# Diagrama-Eduproto.net
KiCad netlist of a schematic drawn in EAGLE
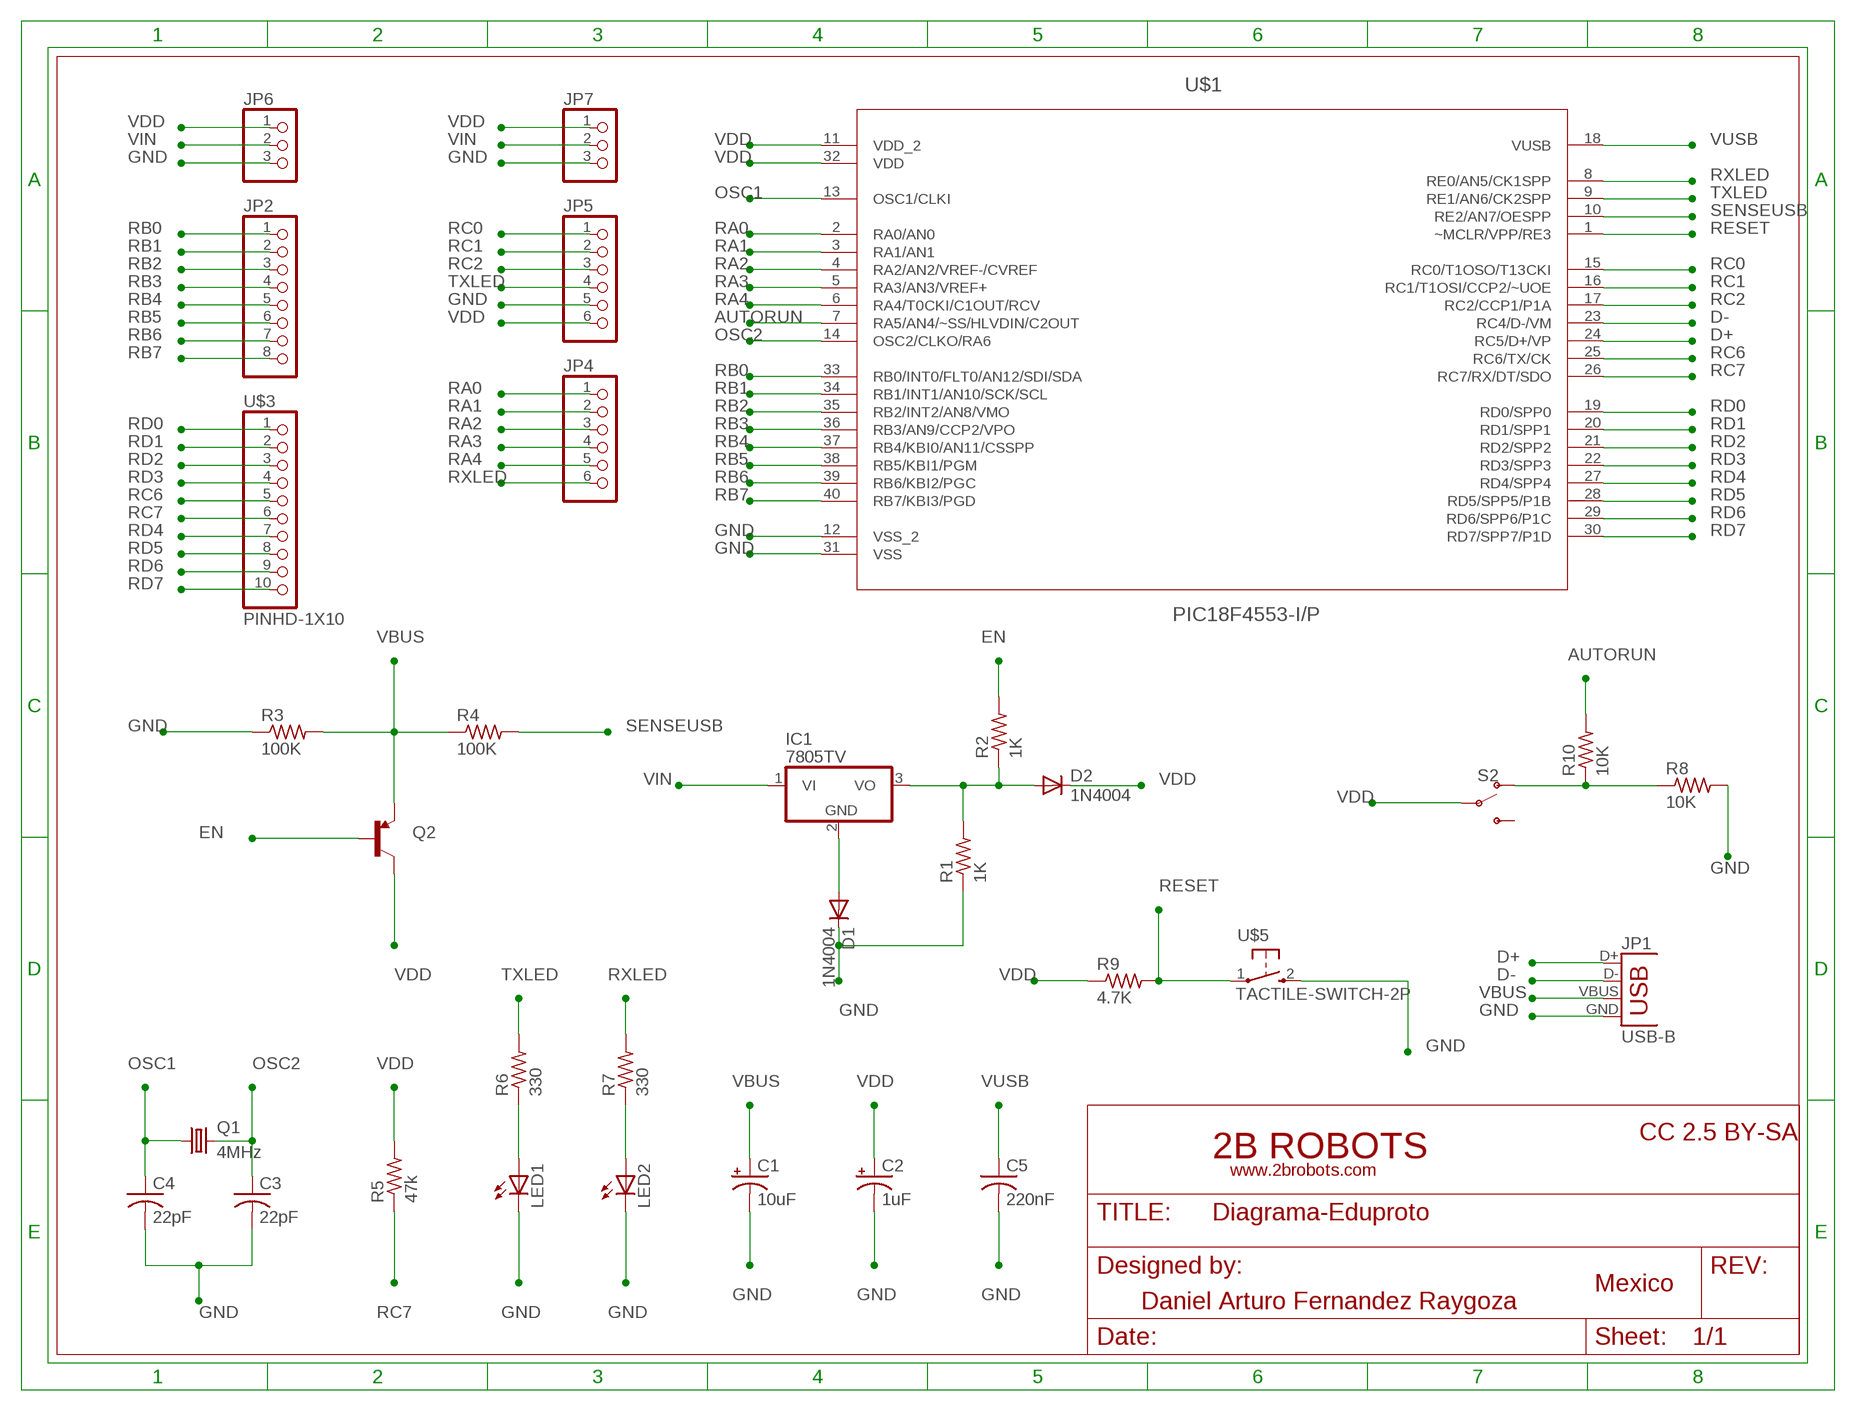
[diagram p0: schematic, sheet 1]

(export (version "E")
  (design (tool "Eeschema 10.0.6"))
  (components
    (comp (ref "C1")
      (value "10uF")
      (footprint "eagle-import:E1,8-4")
      (libsource (lib "eagle-import") (part "CPOL-USE1.8-4"))
    )
    (comp (ref "C2")
      (value "1uF")
      (footprint "eagle-import:E1,8-4")
      (libsource (lib "eagle-import") (part "CPOL-USE1.8-4"))
    )
    (comp (ref "C3")
      (value "22pF")
      (footprint "eagle-import:C050-024X044")
      (libsource (lib "eagle-import") (part "C-US050-024X044"))
    )
    (comp (ref "C4")
      (value "22pF")
      (footprint "eagle-import:C050-024X044")
      (libsource (lib "eagle-import") (part "C-US050-024X044"))
    )
    (comp (ref "C5")
      (value "220nF")
      (footprint "eagle-import:C050-025X075")
      (libsource (lib "eagle-import") (part "C-US050-025X075"))
    )
    (comp (ref "D1")
      (value "1N4004")
      (footprint "eagle-import:DO41-10")
      (libsource (lib "eagle-import") (part "1N4004"))
    )
    (comp (ref "D2")
      (value "1N4004")
      (footprint "eagle-import:DO41-10")
      (libsource (lib "eagle-import") (part "1N4004"))
    )
    (comp (ref "IC1")
      (value "7805TV")
      (footprint "eagle-import:TO220V")
      (libsource (lib "eagle-import") (part "78TV05"))
    )
    (comp (ref "JP1")
      (value "USB-B")
      (footprint "eagle-import:USB-B-PTH")
      (libsource (lib "eagle-import") (part "USBPTH"))
    )
    (comp (ref "JP2")
      (value "PINHD-1X8BIG")
      (footprint "eagle-import:1X08-BIG")
      (libsource (lib "eagle-import") (part "PINHD-1X8BIG"))
    )
    (comp (ref "JP4")
      (value "PINHD-1X6B")
      (footprint "eagle-import:1X06-BIG")
      (libsource (lib "eagle-import") (part "PINHD-1X6B"))
    )
    (comp (ref "JP5")
      (value "PINHD-1X6B")
      (footprint "eagle-import:1X06-BIG")
      (libsource (lib "eagle-import") (part "PINHD-1X6B"))
    )
    (comp (ref "JP6")
      (value "PINHD-1X3CB")
      (footprint "eagle-import:1X03-CLEANBIG")
      (libsource (lib "eagle-import") (part "PINHD-1X3CB"))
    )
    (comp (ref "JP7")
      (value "PINHD-1X3CB")
      (footprint "eagle-import:1X03-CLEANBIG")
      (libsource (lib "eagle-import") (part "PINHD-1X3CB"))
    )
    (comp (ref "LED1")
      (value "LED5MM")
      (footprint "eagle-import:LED5MM")
      (libsource (lib "eagle-import") (part "LED5MM"))
    )
    (comp (ref "LED2")
      (value "LED5MM")
      (footprint "eagle-import:LED5MM")
      (libsource (lib "eagle-import") (part "LED5MM"))
    )
    (comp (ref "Q1")
      (value "4MHz")
      (footprint "eagle-import:HC49_S")
      (libsource (lib "eagle-import") (part "CRYSTALHC49S"))
    )
    (comp (ref "Q2")
      (value "TRANSISTOR_PNPTO92")
      (footprint "eagle-import:TO-92")
      (libsource (lib "eagle-import") (part "TRANSISTOR_PNPTO92"))
    )
    (comp (ref "R1")
      (value "1K")
      (footprint "eagle-import:0207_10")
      (libsource (lib "eagle-import") (part "R-US_0207/10"))
    )
    (comp (ref "R2")
      (value "1K")
      (footprint "eagle-import:0207_10")
      (libsource (lib "eagle-import") (part "R-US_0207/10"))
    )
    (comp (ref "R3")
      (value "100K")
      (footprint "eagle-import:0207_10")
      (libsource (lib "eagle-import") (part "R-US_0207/10"))
    )
    (comp (ref "R4")
      (value "100K")
      (footprint "eagle-import:0207_10")
      (libsource (lib "eagle-import") (part "R-US_0207/10"))
    )
    (comp (ref "R5")
      (value "47k")
      (footprint "eagle-import:0207_10")
      (libsource (lib "eagle-import") (part "R-US_0207/10"))
    )
    (comp (ref "R6")
      (value "330")
      (footprint "eagle-import:0207_10")
      (libsource (lib "eagle-import") (part "R-US_0207/10"))
    )
    (comp (ref "R7")
      (value "330")
      (footprint "eagle-import:0207_10")
      (libsource (lib "eagle-import") (part "R-US_0207/10"))
    )
    (comp (ref "R8")
      (value "10K")
      (footprint "eagle-import:0207_10")
      (libsource (lib "eagle-import") (part "R-US_0207/10"))
    )
    (comp (ref "R9")
      (value "4.7K")
      (footprint "eagle-import:0207_10")
      (libsource (lib "eagle-import") (part "R-US_0207/10"))
    )
    (comp (ref "R10")
      (value "10K")
      (footprint "eagle-import:0207_10")
      (libsource (lib "eagle-import") (part "R-US_0207/10"))
    )
    (comp (ref "S2")
      (value "SWITCH-SPDT-PTH-11.6X4.0MM")
      (footprint "eagle-import:SWITCH_SPDT_PTH_11.6X4.0MM")
      (libsource (lib "eagle-import") (part "SWITCH-SPDT-PTH-11.6X4.0MM"))
    )
    (comp (ref "U$1")
      (value "PIC18F4553-I/P")
      (footprint "eagle-import:DIP254P1524X635-40")
      (libsource (lib "eagle-import") (part "PIC18F4553-I/P"))
    )
    (comp (ref "U$3")
      (value "PINHD-1X10")
      (footprint "eagle-import:1X10-BIG")
      (libsource (lib "eagle-import") (part "PINHD-1X10"))
    )
    (comp (ref "U$5")
      (value "TACTILE-SWITCH-2P")
      (footprint "eagle-import:TAC-SWITCH-PTH-2P")
      (libsource (lib "eagle-import") (part "TACTILE-SWITCH-2P"))
    )
  )
  (nets
    (net (code "1") (name "/AUTORUN") (class "Default")
      (node (ref "R10") (pin "2") (pinfunction "2_2") (pintype "passive"))
      (node (ref "U$1") (pin "7") (pinfunction "RA5/AN4/~{SS/HLVDIN/C2OUT}_7") (pintype "bidirectional"))
    )
    (net (code "2") (name "/D+") (class "Default")
      (node (ref "JP1") (pin "D+") (pinfunction "D+_D+") (pintype "bidirectional"))
      (node (ref "U$1") (pin "24") (pinfunction "RC5/D+/VP_24") (pintype "bidirectional"))
    )
    (net (code "3") (name "/D-") (class "Default")
      (node (ref "JP1") (pin "D-") (pinfunction "D-_D-") (pintype "bidirectional"))
      (node (ref "U$1") (pin "23") (pinfunction "RC4/D-/VM_23") (pintype "bidirectional"))
    )
    (net (code "4") (name "/EN") (class "Default")
      (node (ref "Q2") (pin "2") (pinfunction "B_2") (pintype "passive"))
      (node (ref "R2") (pin "2") (pinfunction "2_2") (pintype "passive"))
    )
    (net (code "5") (name "/GND") (class "Default")
      (node (ref "C1") (pin "-") (pinfunction "-_-") (pintype "passive"))
      (node (ref "C2") (pin "-") (pinfunction "-_-") (pintype "passive"))
      (node (ref "C3") (pin "2") (pinfunction "2_2") (pintype "passive"))
      (node (ref "C4") (pin "2") (pinfunction "2_2") (pintype "passive"))
      (node (ref "C5") (pin "2") (pinfunction "2_2") (pintype "passive"))
      (node (ref "D1") (pin "C") (pinfunction "C_C") (pintype "passive"))
      (node (ref "JP1") (pin "GND") (pinfunction "GND_GND") (pintype "bidirectional"))
      (node (ref "JP5") (pin "5") (pinfunction "5_5") (pintype "passive"))
      (node (ref "JP6") (pin "3") (pinfunction "3_3") (pintype "passive"))
      (node (ref "JP7") (pin "3") (pinfunction "3_3") (pintype "passive"))
      (node (ref "LED1") (pin "K") (pinfunction "C_K") (pintype "passive"))
      (node (ref "LED2") (pin "K") (pinfunction "C_K") (pintype "passive"))
      (node (ref "R1") (pin "1") (pinfunction "1_1") (pintype "passive"))
      (node (ref "R3") (pin "1") (pinfunction "1_1") (pintype "passive"))
      (node (ref "R8") (pin "2") (pinfunction "2_2") (pintype "passive"))
      (node (ref "U$1") (pin "12") (pinfunction "VSS_2_12") (pintype "power_in"))
      (node (ref "U$1") (pin "31") (pinfunction "VSS_31") (pintype "power_in"))
      (node (ref "U$5") (pin "2") (pinfunction "3_2") (pintype "passive"))
    )
    (net (code "6") (name "/OSC1") (class "Default")
      (node (ref "C4") (pin "1") (pinfunction "1_1") (pintype "passive"))
      (node (ref "Q1") (pin "1") (pinfunction "1_1") (pintype "passive"))
      (node (ref "U$1") (pin "13") (pinfunction "OSC1/CLKI_13") (pintype "input"))
    )
    (net (code "7") (name "/OSC2") (class "Default")
      (node (ref "C3") (pin "1") (pinfunction "1_1") (pintype "passive"))
      (node (ref "Q1") (pin "2") (pinfunction "2_2") (pintype "passive"))
      (node (ref "U$1") (pin "14") (pinfunction "OSC2/CLKO/RA6_14") (pintype "bidirectional"))
    )
    (net (code "8") (name "/RA0") (class "Default")
      (node (ref "JP4") (pin "1") (pinfunction "1_1") (pintype "passive"))
      (node (ref "U$1") (pin "2") (pinfunction "RA0/AN0_2") (pintype "bidirectional"))
    )
    (net (code "9") (name "/RA1") (class "Default")
      (node (ref "JP4") (pin "2") (pinfunction "2_2") (pintype "passive"))
      (node (ref "U$1") (pin "3") (pinfunction "RA1/AN1_3") (pintype "bidirectional"))
    )
    (net (code "10") (name "/RA2") (class "Default")
      (node (ref "JP4") (pin "3") (pinfunction "3_3") (pintype "passive"))
      (node (ref "U$1") (pin "4") (pinfunction "RA2/AN2/VREF-/CVREF_4") (pintype "bidirectional"))
    )
    (net (code "11") (name "/RA3") (class "Default")
      (node (ref "JP4") (pin "4") (pinfunction "4_4") (pintype "passive"))
      (node (ref "U$1") (pin "5") (pinfunction "RA3/AN3/VREF+_5") (pintype "bidirectional"))
    )
    (net (code "12") (name "/RA4") (class "Default")
      (node (ref "JP4") (pin "5") (pinfunction "5_5") (pintype "passive"))
      (node (ref "U$1") (pin "6") (pinfunction "RA4/T0CKI/C1OUT/RCV_6") (pintype "bidirectional"))
    )
    (net (code "13") (name "/RB0") (class "Default")
      (node (ref "JP2") (pin "1") (pinfunction "1_1") (pintype "passive"))
      (node (ref "U$1") (pin "33") (pinfunction "RB0/INT0/FLT0/AN12/SDI/SDA_33") (pintype "bidirectional"))
    )
    (net (code "14") (name "/RB1") (class "Default")
      (node (ref "JP2") (pin "2") (pinfunction "2_2") (pintype "passive"))
      (node (ref "U$1") (pin "34") (pinfunction "RB1/INT1/AN10/SCK/SCL_34") (pintype "bidirectional"))
    )
    (net (code "15") (name "/RB2") (class "Default")
      (node (ref "JP2") (pin "3") (pinfunction "3_3") (pintype "passive"))
      (node (ref "U$1") (pin "35") (pinfunction "RB2/INT2/AN8/VMO_35") (pintype "bidirectional"))
    )
    (net (code "16") (name "/RB3") (class "Default")
      (node (ref "JP2") (pin "4") (pinfunction "4_4") (pintype "passive"))
      (node (ref "U$1") (pin "36") (pinfunction "RB3/AN9/CCP2/VPO_36") (pintype "bidirectional"))
    )
    (net (code "17") (name "/RB4") (class "Default")
      (node (ref "JP2") (pin "5") (pinfunction "5_5") (pintype "passive"))
      (node (ref "U$1") (pin "37") (pinfunction "RB4/KBI0/AN11/CSSPP_37") (pintype "bidirectional"))
    )
    (net (code "18") (name "/RB5") (class "Default")
      (node (ref "JP2") (pin "6") (pinfunction "6_6") (pintype "passive"))
      (node (ref "U$1") (pin "38") (pinfunction "RB5/KBI1/PGM_38") (pintype "bidirectional"))
    )
    (net (code "19") (name "/RB6") (class "Default")
      (node (ref "JP2") (pin "7") (pinfunction "7_7") (pintype "passive"))
      (node (ref "U$1") (pin "39") (pinfunction "RB6/KBI2/PGC_39") (pintype "bidirectional"))
    )
    (net (code "20") (name "/RB7") (class "Default")
      (node (ref "JP2") (pin "8") (pinfunction "8_8") (pintype "passive"))
      (node (ref "U$1") (pin "40") (pinfunction "RB7/KBI3/PGD_40") (pintype "bidirectional"))
    )
    (net (code "21") (name "/RC0") (class "Default")
      (node (ref "JP5") (pin "1") (pinfunction "1_1") (pintype "passive"))
      (node (ref "U$1") (pin "15") (pinfunction "RC0/T1OSO/T13CKI_15") (pintype "bidirectional"))
    )
    (net (code "22") (name "/RC1") (class "Default")
      (node (ref "JP5") (pin "2") (pinfunction "2_2") (pintype "passive"))
      (node (ref "U$1") (pin "16") (pinfunction "RC1/T1OSI/CCP2/~{UOE}_16") (pintype "bidirectional"))
    )
    (net (code "23") (name "/RC2") (class "Default")
      (node (ref "JP5") (pin "3") (pinfunction "3_3") (pintype "passive"))
      (node (ref "U$1") (pin "17") (pinfunction "RC2/CCP1/P1A_17") (pintype "bidirectional"))
    )
    (net (code "24") (name "/RC6") (class "Default")
      (node (ref "U$1") (pin "25") (pinfunction "RC6/TX/CK_25") (pintype "bidirectional"))
      (node (ref "U$3") (pin "5") (pinfunction "5_5") (pintype "passive"))
    )
    (net (code "25") (name "/RC7") (class "Default")
      (node (ref "R5") (pin "1") (pinfunction "1_1") (pintype "passive"))
      (node (ref "U$1") (pin "26") (pinfunction "RC7/RX/DT/SDO_26") (pintype "bidirectional"))
      (node (ref "U$3") (pin "6") (pinfunction "6_6") (pintype "passive"))
    )
    (net (code "26") (name "/RD0") (class "Default")
      (node (ref "U$1") (pin "19") (pinfunction "RD0/SPP0_19") (pintype "bidirectional"))
      (node (ref "U$3") (pin "1") (pinfunction "1_1") (pintype "passive"))
    )
    (net (code "27") (name "/RD1") (class "Default")
      (node (ref "U$1") (pin "20") (pinfunction "RD1/SPP1_20") (pintype "bidirectional"))
      (node (ref "U$3") (pin "2") (pinfunction "2_2") (pintype "passive"))
    )
    (net (code "28") (name "/RD2") (class "Default")
      (node (ref "U$1") (pin "21") (pinfunction "RD2/SPP2_21") (pintype "bidirectional"))
      (node (ref "U$3") (pin "3") (pinfunction "3_3") (pintype "passive"))
    )
    (net (code "29") (name "/RD3") (class "Default")
      (node (ref "U$1") (pin "22") (pinfunction "RD3/SPP3_22") (pintype "bidirectional"))
      (node (ref "U$3") (pin "4") (pinfunction "4_4") (pintype "passive"))
    )
    (net (code "30") (name "/RD4") (class "Default")
      (node (ref "U$1") (pin "27") (pinfunction "RD4/SPP4_27") (pintype "bidirectional"))
      (node (ref "U$3") (pin "7") (pinfunction "7_7") (pintype "passive"))
    )
    (net (code "31") (name "/RD5") (class "Default")
      (node (ref "U$1") (pin "28") (pinfunction "RD5/SPP5/P1B_28") (pintype "bidirectional"))
      (node (ref "U$3") (pin "8") (pinfunction "8_8") (pintype "passive"))
    )
    (net (code "32") (name "/RD6") (class "Default")
      (node (ref "U$1") (pin "29") (pinfunction "RD6/SPP6/P1C_29") (pintype "bidirectional"))
      (node (ref "U$3") (pin "9") (pinfunction "9_9") (pintype "passive"))
    )
    (net (code "33") (name "/RD7") (class "Default")
      (node (ref "U$1") (pin "30") (pinfunction "RD7/SPP7/P1D_30") (pintype "bidirectional"))
      (node (ref "U$3") (pin "10") (pinfunction "10_10") (pintype "passive"))
    )
    (net (code "34") (name "/RESET") (class "Default")
      (node (ref "R9") (pin "2") (pinfunction "2_2") (pintype "passive"))
      (node (ref "U$1") (pin "1") (pinfunction "~{MCLR/VPP/RE3}_1") (pintype "input"))
      (node (ref "U$5") (pin "1") (pinfunction "1_1") (pintype "passive"))
    )
    (net (code "35") (name "/RXLED") (class "Default")
      (node (ref "JP4") (pin "6") (pinfunction "6_6") (pintype "passive"))
      (node (ref "R7") (pin "2") (pinfunction "2_2") (pintype "passive"))
      (node (ref "U$1") (pin "8") (pinfunction "RE0/AN5/CK1SPP_8") (pintype "bidirectional"))
    )
    (net (code "36") (name "/SENSEUSB") (class "Default")
      (node (ref "R4") (pin "2") (pinfunction "2_2") (pintype "passive"))
      (node (ref "U$1") (pin "10") (pinfunction "RE2/AN7/OESPP_10") (pintype "bidirectional"))
    )
    (net (code "37") (name "/TXLED") (class "Default")
      (node (ref "JP5") (pin "4") (pinfunction "4_4") (pintype "passive"))
      (node (ref "R6") (pin "2") (pinfunction "2_2") (pintype "passive"))
      (node (ref "U$1") (pin "9") (pinfunction "RE1/AN6/CK2SPP_9") (pintype "bidirectional"))
    )
    (net (code "38") (name "/VBUS") (class "Default")
      (node (ref "C1") (pin "+") (pinfunction "+_+") (pintype "passive"))
      (node (ref "JP1") (pin "VBUS") (pinfunction "VBUS_VBUS") (pintype "bidirectional"))
      (node (ref "Q2") (pin "1") (pinfunction "E_1") (pintype "passive"))
      (node (ref "R3") (pin "2") (pinfunction "2_2") (pintype "passive"))
      (node (ref "R4") (pin "1") (pinfunction "1_1") (pintype "passive"))
    )
    (net (code "39") (name "/VDD") (class "Default")
      (node (ref "C2") (pin "+") (pinfunction "+_+") (pintype "passive"))
      (node (ref "D2") (pin "C") (pinfunction "C_C") (pintype "passive"))
      (node (ref "JP5") (pin "6") (pinfunction "6_6") (pintype "passive"))
      (node (ref "JP6") (pin "1") (pinfunction "1_1") (pintype "passive"))
      (node (ref "JP7") (pin "1") (pinfunction "1_1") (pintype "passive"))
      (node (ref "Q2") (pin "3") (pinfunction "C_3") (pintype "passive"))
      (node (ref "R5") (pin "2") (pinfunction "2_2") (pintype "passive"))
      (node (ref "R9") (pin "1") (pinfunction "1_1") (pintype "passive"))
      (node (ref "S2") (pin "2") (pinfunction "P_2") (pintype "passive"))
      (node (ref "U$1") (pin "11") (pinfunction "VDD_2_11") (pintype "power_in"))
      (node (ref "U$1") (pin "32") (pinfunction "VDD_32") (pintype "power_in"))
    )
    (net (code "40") (name "/VIN") (class "Default")
      (node (ref "IC1") (pin "1") (pinfunction "VI_1") (pintype "input"))
      (node (ref "JP6") (pin "2") (pinfunction "2_2") (pintype "passive"))
      (node (ref "JP7") (pin "2") (pinfunction "2_2") (pintype "passive"))
    )
    (net (code "41") (name "/VUSB") (class "Default")
      (node (ref "C5") (pin "1") (pinfunction "1_1") (pintype "passive"))
      (node (ref "U$1") (pin "18") (pinfunction "VUSB_18") (pintype "bidirectional"))
    )
    (net (code "42") (name "Net-(IC1-GND)") (class "Default")
      (node (ref "D1") (pin "A") (pinfunction "A_A") (pintype "passive"))
      (node (ref "IC1") (pin "2") (pinfunction "GND_2") (pintype "passive"))
    )
    (net (code "43") (name "Net-(IC1-VO)") (class "Default")
      (node (ref "D2") (pin "A") (pinfunction "A_A") (pintype "passive"))
      (node (ref "IC1") (pin "3") (pinfunction "VO_3") (pintype "passive"))
      (node (ref "R1") (pin "2") (pinfunction "2_2") (pintype "passive"))
      (node (ref "R2") (pin "1") (pinfunction "1_1") (pintype "passive"))
    )
    (net (code "44") (name "Net-(LED1-PadA)") (class "Default")
      (node (ref "LED1") (pin "A") (pinfunction "A_A") (pintype "passive"))
      (node (ref "R6") (pin "1") (pinfunction "1_1") (pintype "passive"))
    )
    (net (code "45") (name "Net-(LED2-PadA)") (class "Default")
      (node (ref "LED2") (pin "A") (pinfunction "A_A") (pintype "passive"))
      (node (ref "R7") (pin "1") (pinfunction "1_1") (pintype "passive"))
    )
    (net (code "46") (name "Net-(S2-O)") (class "Default")
      (node (ref "R10") (pin "1") (pinfunction "1_1") (pintype "passive"))
      (node (ref "R8") (pin "1") (pinfunction "1_1") (pintype "passive"))
      (node (ref "S2") (pin "1") (pinfunction "O_1") (pintype "passive"))
    )
    (net (code "47") (name "unconnected-(S2-S-Pad3)") (class "Default")
      (node (ref "S2") (pin "3") (pinfunction "S_3") (pintype "passive"))
    )
  )
)
